# ServoV2.net
KiCad netlist of a schematic drawn in EAGLE
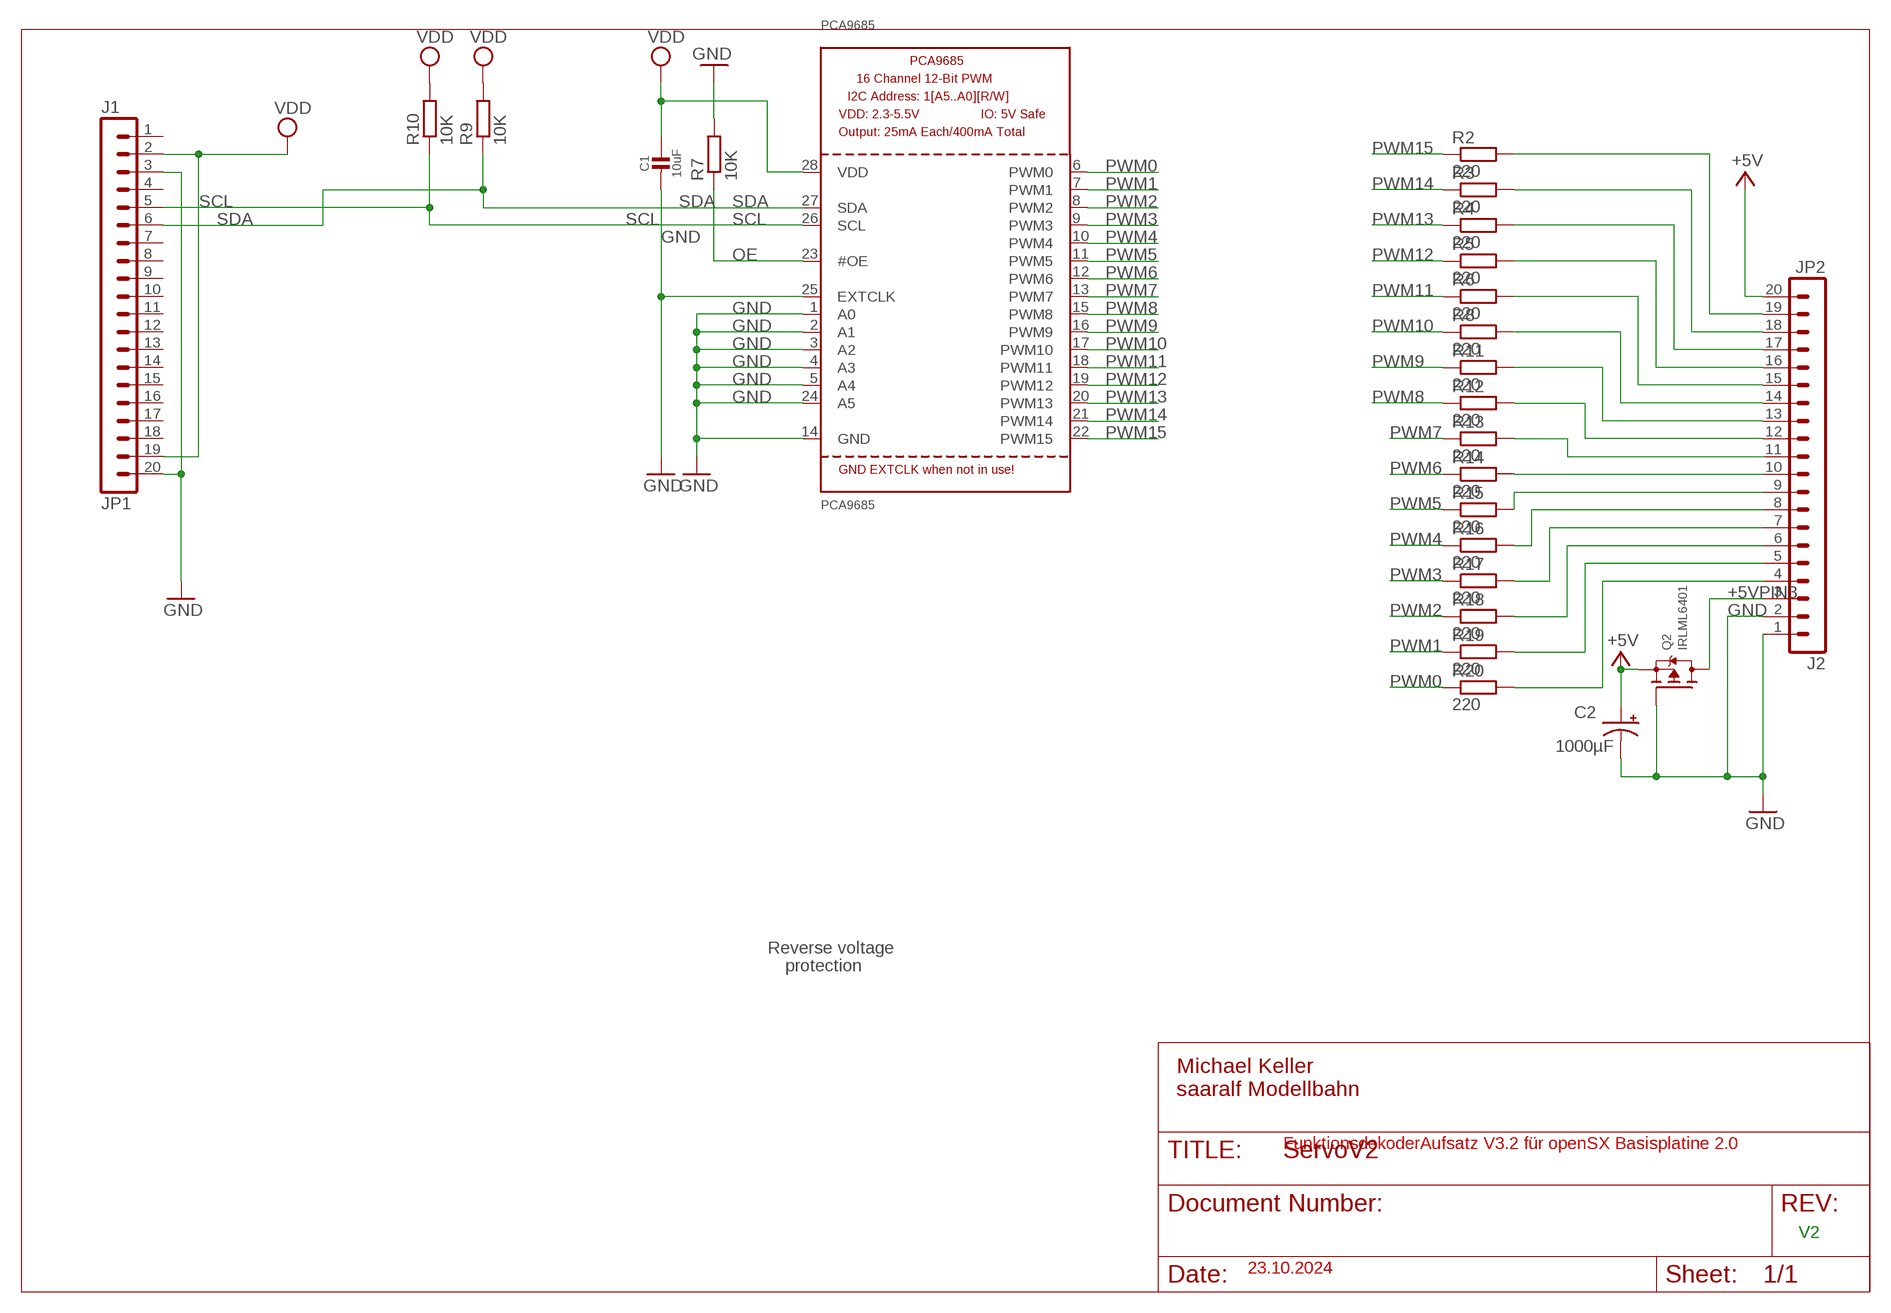
[diagram p0: schematic, sheet 1]

(export (version "E")
  (design (tool "Eeschema 10.0.6"))
  (components
    (comp (ref "C1")
      (value "10uF")
      (footprint "eagle-import:0805-NO")
      (libsource (lib "eagle-import") (part "CAP_CERAMIC0805-NOOUTLINE"))
    )
    (comp (ref "C2")
      (value "1000µF")
      (footprint "eagle-import:E3,5-8")
      (libsource (lib "eagle-import") (part "CPOL-USE3.5-8"))
    )
    (comp (ref "JP1")
      (value "J1")
      (footprint "eagle-import:MA20-1")
      (libsource (lib "eagle-import") (part "MA20-1"))
    )
    (comp (ref "JP2")
      (value "J2")
      (footprint "eagle-import:MA20-1")
      (libsource (lib "eagle-import") (part "MA20-1"))
    )
    (comp (ref "PCA9685")
      (value "PCA9685")
      (footprint "eagle-import:TSSOP28")
      (libsource (lib "eagle-import") (part "PCA9685"))
    )
    (comp (ref "Q2")
      (value "IRLML6401")
      (footprint "eagle-import:SOT23-WIDE")
      (libsource (lib "eagle-import") (part "MOSFET-PWIDE"))
    )
    (comp (ref "R2")
      (value "220")
      (footprint "eagle-import:M0805")
      (libsource (lib "eagle-import") (part "R-EU_M0805"))
    )
    (comp (ref "R3")
      (value "220")
      (footprint "eagle-import:M0805")
      (libsource (lib "eagle-import") (part "R-EU_M0805"))
    )
    (comp (ref "R4")
      (value "220")
      (footprint "eagle-import:M0805")
      (libsource (lib "eagle-import") (part "R-EU_M0805"))
    )
    (comp (ref "R5")
      (value "220")
      (footprint "eagle-import:M0805")
      (libsource (lib "eagle-import") (part "R-EU_M0805"))
    )
    (comp (ref "R6")
      (value "220")
      (footprint "eagle-import:M0805")
      (libsource (lib "eagle-import") (part "R-EU_M0805"))
    )
    (comp (ref "R7")
      (value "10K")
      (footprint "eagle-import:M0805")
      (libsource (lib "eagle-import") (part "R-EU_M0805"))
    )
    (comp (ref "R8")
      (value "220")
      (footprint "eagle-import:M0805")
      (libsource (lib "eagle-import") (part "R-EU_M0805"))
    )
    (comp (ref "R9")
      (value "10K")
      (footprint "eagle-import:M0805")
      (libsource (lib "eagle-import") (part "R-EU_M0805"))
    )
    (comp (ref "R10")
      (value "10K")
      (footprint "eagle-import:M0805")
      (libsource (lib "eagle-import") (part "R-EU_M0805"))
    )
    (comp (ref "R11")
      (value "220")
      (footprint "eagle-import:M0805")
      (libsource (lib "eagle-import") (part "R-EU_M0805"))
    )
    (comp (ref "R12")
      (value "220")
      (footprint "eagle-import:M0805")
      (libsource (lib "eagle-import") (part "R-EU_M0805"))
    )
    (comp (ref "R13")
      (value "220")
      (footprint "eagle-import:M0805")
      (libsource (lib "eagle-import") (part "R-EU_M0805"))
    )
    (comp (ref "R14")
      (value "220")
      (footprint "eagle-import:M0805")
      (libsource (lib "eagle-import") (part "R-EU_M0805"))
    )
    (comp (ref "R15")
      (value "220")
      (footprint "eagle-import:M0805")
      (libsource (lib "eagle-import") (part "R-EU_M0805"))
    )
    (comp (ref "R16")
      (value "220")
      (footprint "eagle-import:M0805")
      (libsource (lib "eagle-import") (part "R-EU_M0805"))
    )
    (comp (ref "R17")
      (value "220")
      (footprint "eagle-import:M0805")
      (libsource (lib "eagle-import") (part "R-EU_M0805"))
    )
    (comp (ref "R18")
      (value "220")
      (footprint "eagle-import:M0805")
      (libsource (lib "eagle-import") (part "R-EU_M0805"))
    )
    (comp (ref "R19")
      (value "220")
      (footprint "eagle-import:M0805")
      (libsource (lib "eagle-import") (part "R-EU_M0805"))
    )
    (comp (ref "R20")
      (value "220")
      (footprint "eagle-import:M0805")
      (libsource (lib "eagle-import") (part "R-EU_M0805"))
    )
  )
  (nets
    (net (code "1") (name "+5V") (class "Default")
      (node (ref "C2") (pin "+") (pinfunction "+_+") (pintype "passive"))
      (node (ref "JP2") (pin "20") (pinfunction "20_20") (pintype "passive"))
      (node (ref "Q2") (pin "2") (pinfunction "S_2") (pintype "passive"))
    )
    (net (code "2") (name "/+5VPIN3") (class "Default")
      (node (ref "JP2") (pin "3") (pinfunction "3_3") (pintype "passive"))
      (node (ref "Q2") (pin "3") (pinfunction "D_3") (pintype "passive"))
    )
    (net (code "3") (name "/OE") (class "Default")
      (node (ref "PCA9685") (pin "23") (pinfunction "#OE_23") (pintype "input"))
      (node (ref "R7") (pin "1") (pinfunction "1_1") (pintype "passive"))
    )
    (net (code "4") (name "/PWM0") (class "Default")
      (node (ref "PCA9685") (pin "6") (pinfunction "PWM0_6") (pintype "output"))
      (node (ref "R20") (pin "1") (pinfunction "1_1") (pintype "passive"))
    )
    (net (code "5") (name "/PWM1") (class "Default")
      (node (ref "PCA9685") (pin "7") (pinfunction "PWM1_7") (pintype "output"))
      (node (ref "R19") (pin "1") (pinfunction "1_1") (pintype "passive"))
    )
    (net (code "6") (name "/PWM2") (class "Default")
      (node (ref "PCA9685") (pin "8") (pinfunction "PWM2_8") (pintype "output"))
      (node (ref "R18") (pin "1") (pinfunction "1_1") (pintype "passive"))
    )
    (net (code "7") (name "/PWM3") (class "Default")
      (node (ref "PCA9685") (pin "9") (pinfunction "PWM3_9") (pintype "output"))
      (node (ref "R17") (pin "1") (pinfunction "1_1") (pintype "passive"))
    )
    (net (code "8") (name "/PWM4") (class "Default")
      (node (ref "PCA9685") (pin "10") (pinfunction "PWM4_10") (pintype "output"))
      (node (ref "R16") (pin "1") (pinfunction "1_1") (pintype "passive"))
    )
    (net (code "9") (name "/PWM5") (class "Default")
      (node (ref "PCA9685") (pin "11") (pinfunction "PWM5_11") (pintype "output"))
      (node (ref "R15") (pin "1") (pinfunction "1_1") (pintype "passive"))
    )
    (net (code "10") (name "/PWM6") (class "Default")
      (node (ref "PCA9685") (pin "12") (pinfunction "PWM6_12") (pintype "output"))
      (node (ref "R14") (pin "1") (pinfunction "1_1") (pintype "passive"))
    )
    (net (code "11") (name "/PWM7") (class "Default")
      (node (ref "PCA9685") (pin "13") (pinfunction "PWM7_13") (pintype "output"))
      (node (ref "R13") (pin "1") (pinfunction "1_1") (pintype "passive"))
    )
    (net (code "12") (name "/PWM8") (class "Default")
      (node (ref "PCA9685") (pin "15") (pinfunction "PWM8_15") (pintype "output"))
      (node (ref "R12") (pin "1") (pinfunction "1_1") (pintype "passive"))
    )
    (net (code "13") (name "/PWM9") (class "Default")
      (node (ref "PCA9685") (pin "16") (pinfunction "PWM9_16") (pintype "output"))
      (node (ref "R11") (pin "1") (pinfunction "1_1") (pintype "passive"))
    )
    (net (code "14") (name "/PWM10") (class "Default")
      (node (ref "PCA9685") (pin "17") (pinfunction "PWM10_17") (pintype "output"))
      (node (ref "R8") (pin "1") (pinfunction "1_1") (pintype "passive"))
    )
    (net (code "15") (name "/PWM11") (class "Default")
      (node (ref "PCA9685") (pin "18") (pinfunction "PWM11_18") (pintype "output"))
      (node (ref "R6") (pin "1") (pinfunction "1_1") (pintype "passive"))
    )
    (net (code "16") (name "/PWM12") (class "Default")
      (node (ref "PCA9685") (pin "19") (pinfunction "PWM12_19") (pintype "output"))
      (node (ref "R5") (pin "1") (pinfunction "1_1") (pintype "passive"))
    )
    (net (code "17") (name "/PWM13") (class "Default")
      (node (ref "PCA9685") (pin "20") (pinfunction "PWM13_20") (pintype "output"))
      (node (ref "R4") (pin "1") (pinfunction "1_1") (pintype "passive"))
    )
    (net (code "18") (name "/PWM14") (class "Default")
      (node (ref "PCA9685") (pin "21") (pinfunction "PWM14_21") (pintype "output"))
      (node (ref "R3") (pin "1") (pinfunction "1_1") (pintype "passive"))
    )
    (net (code "19") (name "/PWM15") (class "Default")
      (node (ref "PCA9685") (pin "22") (pinfunction "PWM15_22") (pintype "output"))
      (node (ref "R2") (pin "1") (pinfunction "1_1") (pintype "passive"))
    )
    (net (code "20") (name "/SCL") (class "Default")
      (node (ref "JP1") (pin "5") (pinfunction "5_5") (pintype "passive"))
      (node (ref "PCA9685") (pin "26") (pinfunction "SCL_26") (pintype "bidirectional"))
      (node (ref "R10") (pin "1") (pinfunction "1_1") (pintype "passive"))
    )
    (net (code "21") (name "/SDA") (class "Default")
      (node (ref "JP1") (pin "6") (pinfunction "6_6") (pintype "passive"))
      (node (ref "PCA9685") (pin "27") (pinfunction "SDA_27") (pintype "bidirectional"))
      (node (ref "R9") (pin "1") (pinfunction "1_1") (pintype "passive"))
    )
    (net (code "22") (name "GND") (class "Default")
      (node (ref "C1") (pin "2") (pinfunction "2_2") (pintype "passive"))
      (node (ref "C2") (pin "-") (pinfunction "-_-") (pintype "passive"))
      (node (ref "JP1") (pin "20") (pinfunction "20_20") (pintype "passive"))
      (node (ref "JP1") (pin "3") (pinfunction "3_3") (pintype "passive"))
      (node (ref "JP2") (pin "1") (pinfunction "1_1") (pintype "passive"))
      (node (ref "JP2") (pin "2") (pinfunction "2_2") (pintype "passive"))
      (node (ref "PCA9685") (pin "1") (pinfunction "A0_1") (pintype "bidirectional"))
      (node (ref "PCA9685") (pin "14") (pinfunction "GND_14") (pintype "power_in"))
      (node (ref "PCA9685") (pin "2") (pinfunction "A1_2") (pintype "bidirectional"))
      (node (ref "PCA9685") (pin "24") (pinfunction "A5_24") (pintype "bidirectional"))
      (node (ref "PCA9685") (pin "25") (pinfunction "EXTCLK_25") (pintype "input"))
      (node (ref "PCA9685") (pin "3") (pinfunction "A2_3") (pintype "bidirectional"))
      (node (ref "PCA9685") (pin "4") (pinfunction "A3_4") (pintype "bidirectional"))
      (node (ref "PCA9685") (pin "5") (pinfunction "A4_5") (pintype "bidirectional"))
      (node (ref "Q2") (pin "1") (pinfunction "G_1") (pintype "passive"))
      (node (ref "R7") (pin "2") (pinfunction "2_2") (pintype "passive"))
    )
    (net (code "23") (name "Net-(JP2-Pad4)") (class "Default")
      (node (ref "JP2") (pin "4") (pinfunction "4_4") (pintype "passive"))
      (node (ref "R20") (pin "2") (pinfunction "2_2") (pintype "passive"))
    )
    (net (code "24") (name "Net-(JP2-Pad5)") (class "Default")
      (node (ref "JP2") (pin "5") (pinfunction "5_5") (pintype "passive"))
      (node (ref "R19") (pin "2") (pinfunction "2_2") (pintype "passive"))
    )
    (net (code "25") (name "Net-(JP2-Pad6)") (class "Default")
      (node (ref "JP2") (pin "6") (pinfunction "6_6") (pintype "passive"))
      (node (ref "R18") (pin "2") (pinfunction "2_2") (pintype "passive"))
    )
    (net (code "26") (name "Net-(JP2-Pad7)") (class "Default")
      (node (ref "JP2") (pin "7") (pinfunction "7_7") (pintype "passive"))
      (node (ref "R17") (pin "2") (pinfunction "2_2") (pintype "passive"))
    )
    (net (code "27") (name "Net-(JP2-Pad8)") (class "Default")
      (node (ref "JP2") (pin "8") (pinfunction "8_8") (pintype "passive"))
      (node (ref "R16") (pin "2") (pinfunction "2_2") (pintype "passive"))
    )
    (net (code "28") (name "Net-(JP2-Pad9)") (class "Default")
      (node (ref "JP2") (pin "9") (pinfunction "9_9") (pintype "passive"))
      (node (ref "R15") (pin "2") (pinfunction "2_2") (pintype "passive"))
    )
    (net (code "29") (name "Net-(JP2-Pad10)") (class "Default")
      (node (ref "JP2") (pin "10") (pinfunction "10_10") (pintype "passive"))
      (node (ref "R14") (pin "2") (pinfunction "2_2") (pintype "passive"))
    )
    (net (code "30") (name "Net-(JP2-Pad11)") (class "Default")
      (node (ref "JP2") (pin "11") (pinfunction "11_11") (pintype "passive"))
      (node (ref "R13") (pin "2") (pinfunction "2_2") (pintype "passive"))
    )
    (net (code "31") (name "Net-(JP2-Pad12)") (class "Default")
      (node (ref "JP2") (pin "12") (pinfunction "12_12") (pintype "passive"))
      (node (ref "R12") (pin "2") (pinfunction "2_2") (pintype "passive"))
    )
    (net (code "32") (name "Net-(JP2-Pad13)") (class "Default")
      (node (ref "JP2") (pin "13") (pinfunction "13_13") (pintype "passive"))
      (node (ref "R11") (pin "2") (pinfunction "2_2") (pintype "passive"))
    )
    (net (code "33") (name "Net-(JP2-Pad14)") (class "Default")
      (node (ref "JP2") (pin "14") (pinfunction "14_14") (pintype "passive"))
      (node (ref "R8") (pin "2") (pinfunction "2_2") (pintype "passive"))
    )
    (net (code "34") (name "Net-(JP2-Pad15)") (class "Default")
      (node (ref "JP2") (pin "15") (pinfunction "15_15") (pintype "passive"))
      (node (ref "R6") (pin "2") (pinfunction "2_2") (pintype "passive"))
    )
    (net (code "35") (name "Net-(JP2-Pad16)") (class "Default")
      (node (ref "JP2") (pin "16") (pinfunction "16_16") (pintype "passive"))
      (node (ref "R5") (pin "2") (pinfunction "2_2") (pintype "passive"))
    )
    (net (code "36") (name "Net-(JP2-Pad17)") (class "Default")
      (node (ref "JP2") (pin "17") (pinfunction "17_17") (pintype "passive"))
      (node (ref "R4") (pin "2") (pinfunction "2_2") (pintype "passive"))
    )
    (net (code "37") (name "Net-(JP2-Pad18)") (class "Default")
      (node (ref "JP2") (pin "18") (pinfunction "18_18") (pintype "passive"))
      (node (ref "R3") (pin "2") (pinfunction "2_2") (pintype "passive"))
    )
    (net (code "38") (name "Net-(JP2-Pad19)") (class "Default")
      (node (ref "JP2") (pin "19") (pinfunction "19_19") (pintype "passive"))
      (node (ref "R2") (pin "2") (pinfunction "2_2") (pintype "passive"))
    )
    (net (code "39") (name "VDD") (class "Default")
      (node (ref "C1") (pin "1") (pinfunction "1_1") (pintype "passive"))
      (node (ref "JP1") (pin "19") (pinfunction "19_19") (pintype "passive"))
      (node (ref "JP1") (pin "2") (pinfunction "2_2") (pintype "passive"))
      (node (ref "PCA9685") (pin "28") (pinfunction "VDD_28") (pintype "power_in"))
      (node (ref "R10") (pin "2") (pinfunction "2_2") (pintype "passive"))
      (node (ref "R9") (pin "2") (pinfunction "2_2") (pintype "passive"))
    )
    (net (code "40") (name "unconnected-(JP1-Pad1)") (class "Default")
      (node (ref "JP1") (pin "1") (pinfunction "1_1") (pintype "passive"))
    )
    (net (code "41") (name "unconnected-(JP1-Pad4)") (class "Default")
      (node (ref "JP1") (pin "4") (pinfunction "4_4") (pintype "passive"))
    )
    (net (code "42") (name "unconnected-(JP1-Pad7)") (class "Default")
      (node (ref "JP1") (pin "7") (pinfunction "7_7") (pintype "passive"))
    )
    (net (code "43") (name "unconnected-(JP1-Pad8)") (class "Default")
      (node (ref "JP1") (pin "8") (pinfunction "8_8") (pintype "passive"))
    )
    (net (code "44") (name "unconnected-(JP1-Pad9)") (class "Default")
      (node (ref "JP1") (pin "9") (pinfunction "9_9") (pintype "passive"))
    )
    (net (code "45") (name "unconnected-(JP1-Pad10)") (class "Default")
      (node (ref "JP1") (pin "10") (pinfunction "10_10") (pintype "passive"))
    )
    (net (code "46") (name "unconnected-(JP1-Pad11)") (class "Default")
      (node (ref "JP1") (pin "11") (pinfunction "11_11") (pintype "passive"))
    )
    (net (code "47") (name "unconnected-(JP1-Pad12)") (class "Default")
      (node (ref "JP1") (pin "12") (pinfunction "12_12") (pintype "passive"))
    )
    (net (code "48") (name "unconnected-(JP1-Pad13)") (class "Default")
      (node (ref "JP1") (pin "13") (pinfunction "13_13") (pintype "passive"))
    )
    (net (code "49") (name "unconnected-(JP1-Pad14)") (class "Default")
      (node (ref "JP1") (pin "14") (pinfunction "14_14") (pintype "passive"))
    )
    (net (code "50") (name "unconnected-(JP1-Pad15)") (class "Default")
      (node (ref "JP1") (pin "15") (pinfunction "15_15") (pintype "passive"))
    )
    (net (code "51") (name "unconnected-(JP1-Pad16)") (class "Default")
      (node (ref "JP1") (pin "16") (pinfunction "16_16") (pintype "passive"))
    )
    (net (code "52") (name "unconnected-(JP1-Pad17)") (class "Default")
      (node (ref "JP1") (pin "17") (pinfunction "17_17") (pintype "passive"))
    )
    (net (code "53") (name "unconnected-(JP1-Pad18)") (class "Default")
      (node (ref "JP1") (pin "18") (pinfunction "18_18") (pintype "passive"))
    )
  )
)
